# 23256_ROM-el_v1.net
KiCad netlist of a schematic drawn in EAGLE
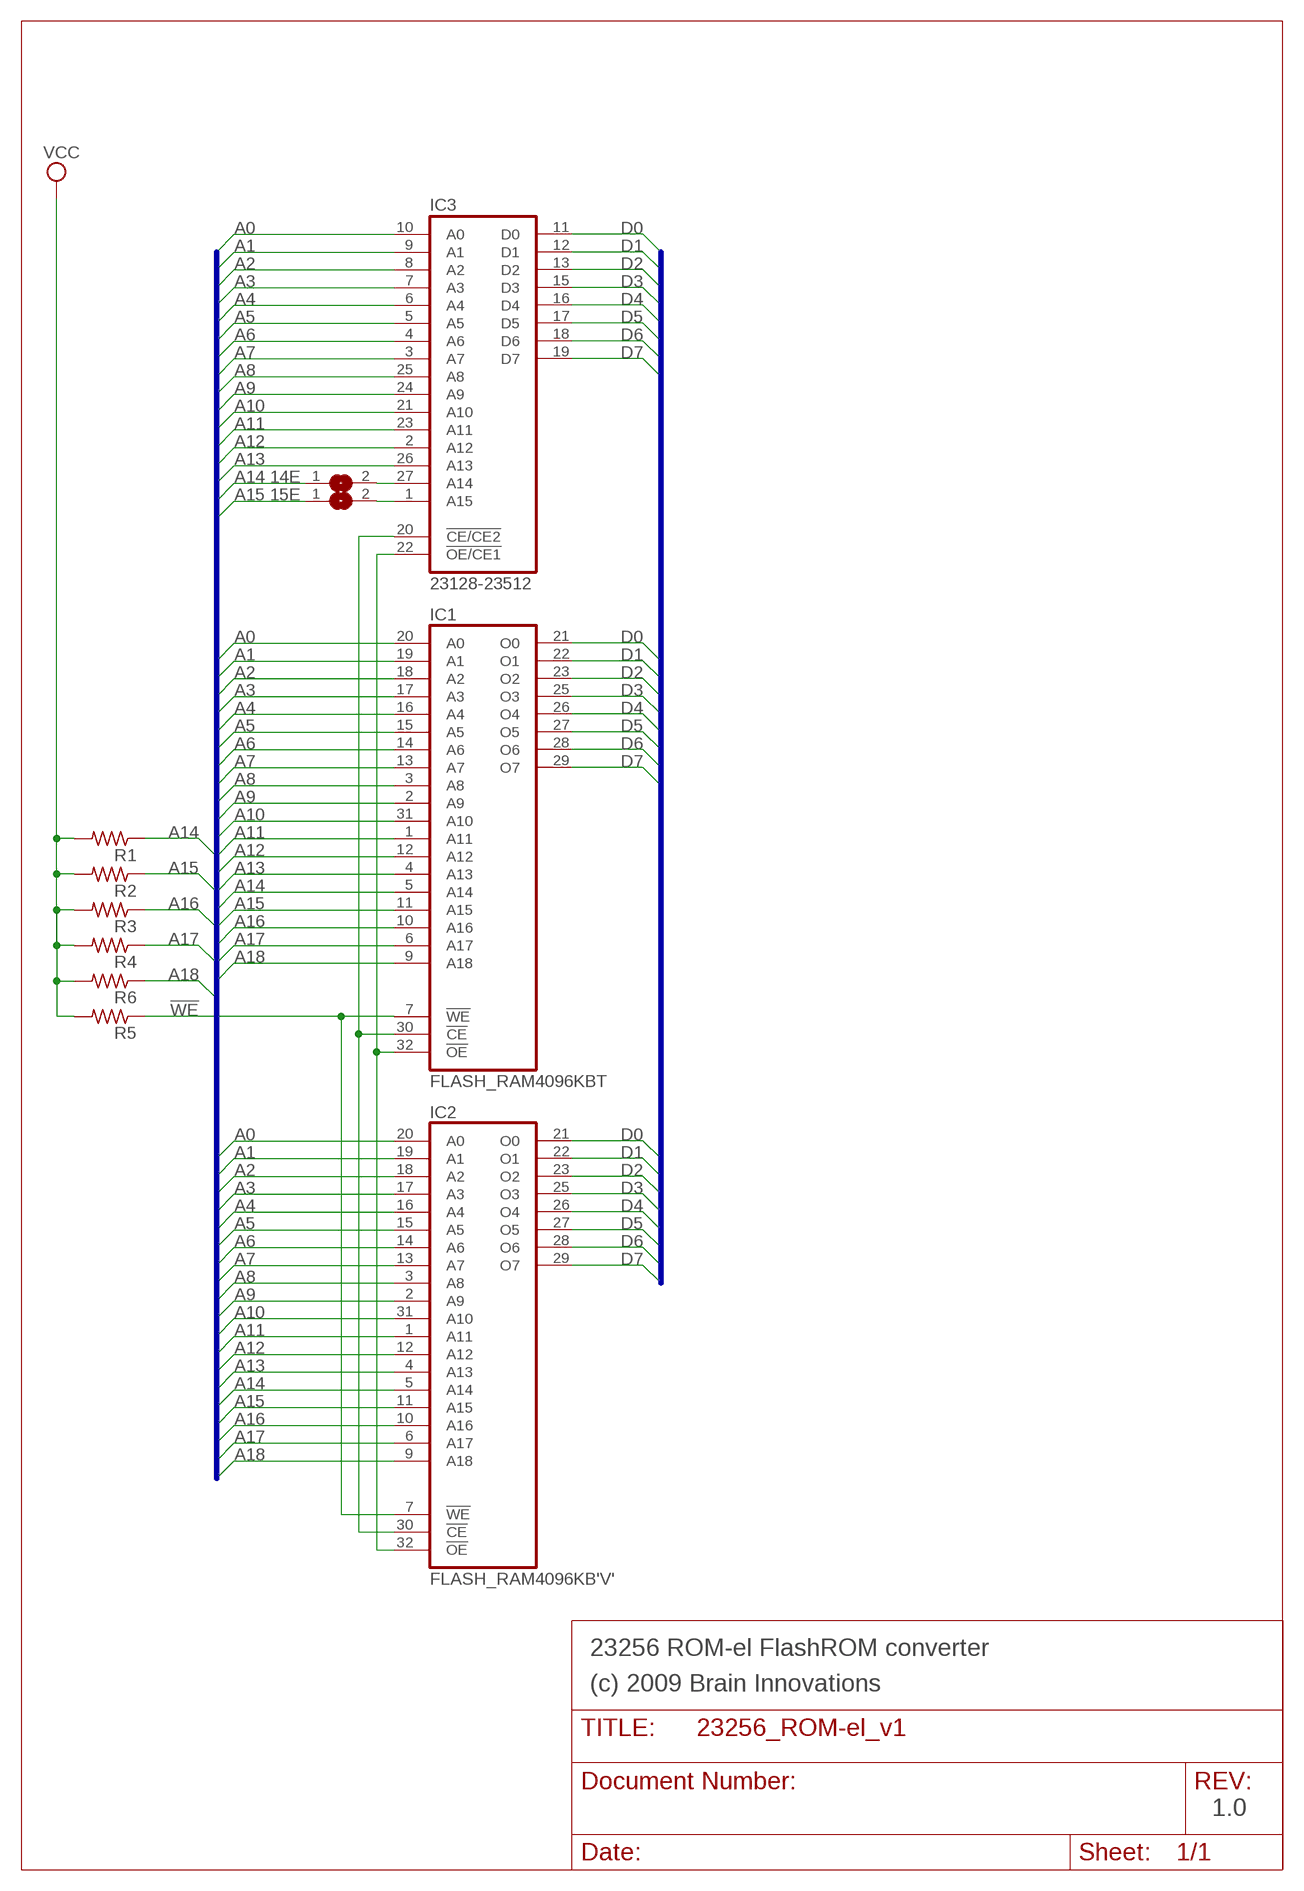
[diagram p0: schematic, sheet 1]

(export (version "E")
  (design (tool "Eeschema 10.0.6"))
  (components
    (comp (ref "14E") (value "SJ") (footprint "eagle-import:SJ") (libsource (lib "eagle-import") (part "SJ")))
    (comp (ref "15E")
      (value "15E")
      (footprint "eagle-import:SJ")
      (libsource (lib "eagle-import") (part "SJ"))
    )
    (comp (ref "IC1")
      (value "FLASH_RAM4096KBT")
      (footprint "eagle-import:TSOP32")
      (libsource (lib "eagle-import") (part "FLASH_RAM4096KB'T'"))
    )
    (comp (ref "IC2")
      (value "FLASH_RAM4096KB'V'")
      (footprint "eagle-import:VSOP32")
      (libsource (lib "eagle-import") (part "FLASH_RAM4096KB'V'"))
    )
    (comp (ref "IC3")
      (value "23128-23512")
      (footprint "eagle-import:DIL28-ROUNDPAD")
      (libsource (lib "eagle-import") (part "23512-RP"))
    )
    (comp (ref "R1")
      (value "R-US_R0805")
      (footprint "eagle-import:R0805")
      (libsource (lib "eagle-import") (part "R-US_R0805"))
    )
    (comp (ref "R2")
      (value "R-US_R0805")
      (footprint "eagle-import:R0805")
      (libsource (lib "eagle-import") (part "R-US_R0805"))
    )
    (comp (ref "R3")
      (value "R-US_R0805")
      (footprint "eagle-import:R0805")
      (libsource (lib "eagle-import") (part "R-US_R0805"))
    )
    (comp (ref "R4")
      (value "R-US_R0805")
      (footprint "eagle-import:R0805")
      (libsource (lib "eagle-import") (part "R-US_R0805"))
    )
    (comp (ref "R5")
      (value "R-US_R0805")
      (footprint "eagle-import:R0805")
      (libsource (lib "eagle-import") (part "R-US_R0805"))
    )
    (comp (ref "R6")
      (value "R-US_R0805")
      (footprint "eagle-import:R0805")
      (libsource (lib "eagle-import") (part "R-US_R0805"))
    )
  )
  (nets
    (net (code "1") (name "/A0") (class "Default")
      (node (ref "IC1") (pin "20") (pinfunction "A0_20") (pintype "input"))
      (node (ref "IC2") (pin "20") (pinfunction "A0_20") (pintype "input"))
      (node (ref "IC3") (pin "10") (pinfunction "A0_10") (pintype "input"))
    )
    (net (code "2") (name "/A1") (class "Default")
      (node (ref "IC1") (pin "19") (pinfunction "A1_19") (pintype "input"))
      (node (ref "IC2") (pin "19") (pinfunction "A1_19") (pintype "input"))
      (node (ref "IC3") (pin "9") (pinfunction "A1_9") (pintype "input"))
    )
    (net (code "3") (name "/A2") (class "Default")
      (node (ref "IC1") (pin "18") (pinfunction "A2_18") (pintype "input"))
      (node (ref "IC2") (pin "18") (pinfunction "A2_18") (pintype "input"))
      (node (ref "IC3") (pin "8") (pinfunction "A2_8") (pintype "input"))
    )
    (net (code "4") (name "/A3") (class "Default")
      (node (ref "IC1") (pin "17") (pinfunction "A3_17") (pintype "input"))
      (node (ref "IC2") (pin "17") (pinfunction "A3_17") (pintype "input"))
      (node (ref "IC3") (pin "7") (pinfunction "A3_7") (pintype "input"))
    )
    (net (code "5") (name "/A4") (class "Default")
      (node (ref "IC1") (pin "16") (pinfunction "A4_16") (pintype "input"))
      (node (ref "IC2") (pin "16") (pinfunction "A4_16") (pintype "input"))
      (node (ref "IC3") (pin "6") (pinfunction "A4_6") (pintype "input"))
    )
    (net (code "6") (name "/A5") (class "Default")
      (node (ref "IC1") (pin "15") (pinfunction "A5_15") (pintype "input"))
      (node (ref "IC2") (pin "15") (pinfunction "A5_15") (pintype "input"))
      (node (ref "IC3") (pin "5") (pinfunction "A5_5") (pintype "input"))
    )
    (net (code "7") (name "/A6") (class "Default")
      (node (ref "IC1") (pin "14") (pinfunction "A6_14") (pintype "input"))
      (node (ref "IC2") (pin "14") (pinfunction "A6_14") (pintype "input"))
      (node (ref "IC3") (pin "4") (pinfunction "A6_4") (pintype "input"))
    )
    (net (code "8") (name "/A7") (class "Default")
      (node (ref "IC1") (pin "13") (pinfunction "A7_13") (pintype "input"))
      (node (ref "IC2") (pin "13") (pinfunction "A7_13") (pintype "input"))
      (node (ref "IC3") (pin "3") (pinfunction "A7_3") (pintype "input"))
    )
    (net (code "9") (name "/A8") (class "Default")
      (node (ref "IC1") (pin "3") (pinfunction "A8_3") (pintype "input"))
      (node (ref "IC2") (pin "3") (pinfunction "A8_3") (pintype "input"))
      (node (ref "IC3") (pin "25") (pinfunction "A8_25") (pintype "input"))
    )
    (net (code "10") (name "/A9") (class "Default")
      (node (ref "IC1") (pin "2") (pinfunction "A9_2") (pintype "input"))
      (node (ref "IC2") (pin "2") (pinfunction "A9_2") (pintype "input"))
      (node (ref "IC3") (pin "24") (pinfunction "A9_24") (pintype "input"))
    )
    (net (code "11") (name "/A10") (class "Default")
      (node (ref "IC1") (pin "31") (pinfunction "A10_31") (pintype "input"))
      (node (ref "IC2") (pin "31") (pinfunction "A10_31") (pintype "input"))
      (node (ref "IC3") (pin "21") (pinfunction "A10_21") (pintype "input"))
    )
    (net (code "12") (name "/A11") (class "Default")
      (node (ref "IC1") (pin "1") (pinfunction "A11_1") (pintype "input"))
      (node (ref "IC2") (pin "1") (pinfunction "A11_1") (pintype "input"))
      (node (ref "IC3") (pin "23") (pinfunction "A11_23") (pintype "input"))
    )
    (net (code "13") (name "/A12") (class "Default")
      (node (ref "IC1") (pin "12") (pinfunction "A12_12") (pintype "input"))
      (node (ref "IC2") (pin "12") (pinfunction "A12_12") (pintype "input"))
      (node (ref "IC3") (pin "2") (pinfunction "A12_2") (pintype "input"))
    )
    (net (code "14") (name "/A13") (class "Default")
      (node (ref "IC1") (pin "4") (pinfunction "A13_4") (pintype "input"))
      (node (ref "IC2") (pin "4") (pinfunction "A13_4") (pintype "input"))
      (node (ref "IC3") (pin "26") (pinfunction "A13_26") (pintype "input"))
    )
    (net (code "15") (name "/A14") (class "Default")
      (node (ref "14E") (pin "1") (pinfunction "1_1") (pintype "passive"))
      (node (ref "IC1") (pin "5") (pinfunction "A14_5") (pintype "input"))
      (node (ref "IC2") (pin "5") (pinfunction "A14_5") (pintype "input"))
      (node (ref "R1") (pin "1") (pinfunction "1_1") (pintype "passive"))
    )
    (net (code "16") (name "/A15") (class "Default")
      (node (ref "15E") (pin "1") (pinfunction "1_1") (pintype "passive"))
      (node (ref "IC1") (pin "11") (pinfunction "A15_11") (pintype "input"))
      (node (ref "IC2") (pin "11") (pinfunction "A15_11") (pintype "input"))
      (node (ref "R2") (pin "1") (pinfunction "1_1") (pintype "passive"))
    )
    (net (code "17") (name "/A16") (class "Default")
      (node (ref "IC1") (pin "10") (pinfunction "A16_10") (pintype "input"))
      (node (ref "IC2") (pin "10") (pinfunction "A16_10") (pintype "input"))
      (node (ref "R3") (pin "1") (pinfunction "1_1") (pintype "passive"))
    )
    (net (code "18") (name "/A17") (class "Default")
      (node (ref "IC1") (pin "6") (pinfunction "A17_6") (pintype "input"))
      (node (ref "IC2") (pin "6") (pinfunction "A17_6") (pintype "input"))
      (node (ref "R4") (pin "1") (pinfunction "1_1") (pintype "passive"))
    )
    (net (code "19") (name "/A18") (class "Default")
      (node (ref "IC1") (pin "9") (pinfunction "A18_9") (pintype "input"))
      (node (ref "IC2") (pin "9") (pinfunction "A18_9") (pintype "input"))
      (node (ref "R6") (pin "1") (pinfunction "1_1") (pintype "passive"))
    )
    (net (code "20") (name "/D0") (class "Default")
      (node (ref "IC1") (pin "21") (pinfunction "O0_21") (pintype "tri_state"))
      (node (ref "IC2") (pin "21") (pinfunction "O0_21") (pintype "tri_state"))
      (node (ref "IC3") (pin "11") (pinfunction "D0_11") (pintype "tri_state"))
    )
    (net (code "21") (name "/D1") (class "Default")
      (node (ref "IC1") (pin "22") (pinfunction "O1_22") (pintype "tri_state"))
      (node (ref "IC2") (pin "22") (pinfunction "O1_22") (pintype "tri_state"))
      (node (ref "IC3") (pin "12") (pinfunction "D1_12") (pintype "tri_state"))
    )
    (net (code "22") (name "/D2") (class "Default")
      (node (ref "IC1") (pin "23") (pinfunction "O2_23") (pintype "tri_state"))
      (node (ref "IC2") (pin "23") (pinfunction "O2_23") (pintype "tri_state"))
      (node (ref "IC3") (pin "13") (pinfunction "D2_13") (pintype "tri_state"))
    )
    (net (code "23") (name "/D3") (class "Default")
      (node (ref "IC1") (pin "25") (pinfunction "O3_25") (pintype "tri_state"))
      (node (ref "IC2") (pin "25") (pinfunction "O3_25") (pintype "tri_state"))
      (node (ref "IC3") (pin "15") (pinfunction "D3_15") (pintype "tri_state"))
    )
    (net (code "24") (name "/D4") (class "Default")
      (node (ref "IC1") (pin "26") (pinfunction "O4_26") (pintype "tri_state"))
      (node (ref "IC2") (pin "26") (pinfunction "O4_26") (pintype "tri_state"))
      (node (ref "IC3") (pin "16") (pinfunction "D4_16") (pintype "tri_state"))
    )
    (net (code "25") (name "/D5") (class "Default")
      (node (ref "IC1") (pin "27") (pinfunction "O5_27") (pintype "tri_state"))
      (node (ref "IC2") (pin "27") (pinfunction "O5_27") (pintype "tri_state"))
      (node (ref "IC3") (pin "17") (pinfunction "D5_17") (pintype "tri_state"))
    )
    (net (code "26") (name "/D6") (class "Default")
      (node (ref "IC1") (pin "28") (pinfunction "O6_28") (pintype "tri_state"))
      (node (ref "IC2") (pin "28") (pinfunction "O6_28") (pintype "tri_state"))
      (node (ref "IC3") (pin "18") (pinfunction "D6_18") (pintype "tri_state"))
    )
    (net (code "27") (name "/D7") (class "Default")
      (node (ref "IC1") (pin "29") (pinfunction "O7_29") (pintype "tri_state"))
      (node (ref "IC2") (pin "29") (pinfunction "O7_29") (pintype "tri_state"))
      (node (ref "IC3") (pin "19") (pinfunction "D7_19") (pintype "tri_state"))
    )
    (net (code "28") (name "/~{WE}") (class "Default")
      (node (ref "IC1") (pin "7") (pinfunction "~{WE}_7") (pintype "input"))
      (node (ref "IC2") (pin "7") (pinfunction "~{WE}_7") (pintype "input"))
      (node (ref "R5") (pin "1") (pinfunction "1_1") (pintype "passive"))
    )
    (net (code "29") (name "Net-(IC1A-~{CE})") (class "Default")
      (node (ref "IC1") (pin "30") (pinfunction "~{CE}_30") (pintype "input"))
      (node (ref "IC2") (pin "30") (pinfunction "~{CE}_30") (pintype "input"))
      (node (ref "IC3") (pin "20") (pinfunction "~{CE/CE2}_20") (pintype "input"))
    )
    (net (code "30") (name "Net-(IC1A-~{OE})") (class "Default")
      (node (ref "IC1") (pin "32") (pinfunction "~{OE}_32") (pintype "input"))
      (node (ref "IC2") (pin "32") (pinfunction "~{OE}_32") (pintype "input"))
      (node (ref "IC3") (pin "22") (pinfunction "~{OE/CE1}_22") (pintype "input"))
    )
    (net (code "31") (name "Net-(IC3A-A14)") (class "Default")
      (node (ref "14E") (pin "2") (pinfunction "2_2") (pintype "passive"))
      (node (ref "IC3") (pin "27") (pinfunction "A14_27") (pintype "input"))
    )
    (net (code "32") (name "Net-(IC3A-A15)") (class "Default")
      (node (ref "15E") (pin "2") (pinfunction "2_2") (pintype "passive"))
      (node (ref "IC3") (pin "1") (pinfunction "A15_1") (pintype "input"))
    )
    (net (code "33") (name "VCC") (class "Default")
      (node (ref "R1") (pin "2") (pinfunction "2_2") (pintype "passive"))
      (node (ref "R2") (pin "2") (pinfunction "2_2") (pintype "passive"))
      (node (ref "R3") (pin "2") (pinfunction "2_2") (pintype "passive"))
      (node (ref "R4") (pin "2") (pinfunction "2_2") (pintype "passive"))
      (node (ref "R5") (pin "2") (pinfunction "2_2") (pintype "passive"))
      (node (ref "R6") (pin "2") (pinfunction "2_2") (pintype "passive"))
    )
  )
)
